# p8x-2016-propplug.net
KiCad netlist of a schematic drawn in EAGLE
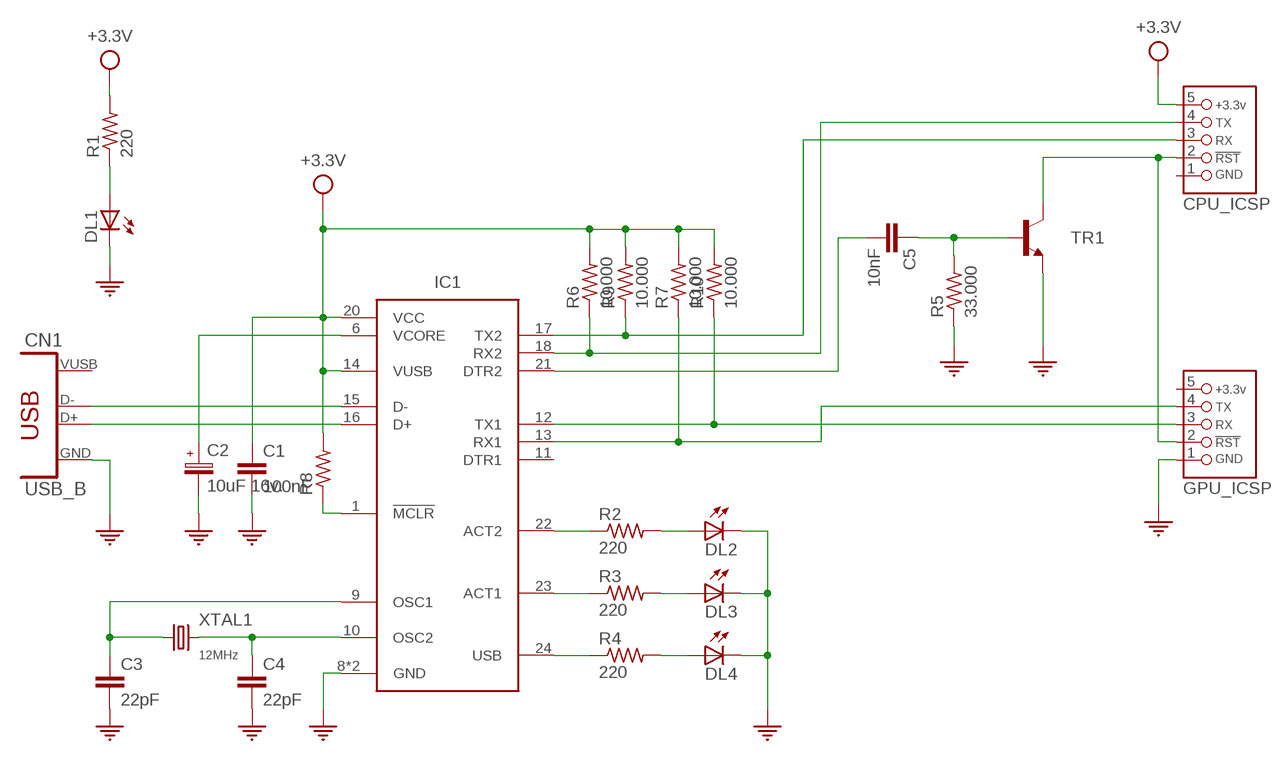
[diagram p0: schematic, sheet 1]

(export (version "E")
  (design (tool "Eeschema 10.0.6"))
  (components
    (comp (ref "C1")
      (value "100nF")
      (footprint "eagle-import:C050-025X075")
      (libsource (lib "eagle-import") (part "C"))
    )
    (comp (ref "C2")
      (value "10uF 16v.")
      (footprint "eagle-import:E2,5-6")
      (libsource (lib "eagle-import") (part "CP-2.5-6"))
    )
    (comp (ref "C3")
      (value "22pF")
      (footprint "eagle-import:C050-025X075D")
      (libsource (lib "eagle-import") (part "C-DISC"))
    )
    (comp (ref "C4")
      (value "22pF")
      (footprint "eagle-import:C050-025X075D")
      (libsource (lib "eagle-import") (part "C-DISC"))
    )
    (comp (ref "C5")
      (value "10nF")
      (footprint "eagle-import:C050-025X075")
      (libsource (lib "eagle-import") (part "C"))
    )
    (comp (ref "CN1")
      (value "USB_B")
      (footprint "eagle-import:USB-B")
      (libsource (lib "eagle-import") (part "USB_B"))
    )
    (comp (ref "CPU_ICSP")
      (value "PROPELLER_ICSP_HEADER")
      (footprint "eagle-import:HEADER_PRG_1X05")
      (libsource (lib "eagle-import") (part "PROPELLER_ICSP_HEADER"))
    )
    (comp (ref "DL1")
      (value "LED-3MM")
      (footprint "eagle-import:LED3MM")
      (libsource (lib "eagle-import") (part "LED-3MM"))
    )
    (comp (ref "DL2")
      (value "LED-3MM")
      (footprint "eagle-import:LED3MM")
      (libsource (lib "eagle-import") (part "LED-3MM"))
    )
    (comp (ref "DL3")
      (value "LED-3MM")
      (footprint "eagle-import:LED3MM")
      (libsource (lib "eagle-import") (part "LED-3MM"))
    )
    (comp (ref "DL4")
      (value "LED-3MM")
      (footprint "eagle-import:LED3MM")
      (libsource (lib "eagle-import") (part "LED-3MM"))
    )
    (comp (ref "GPU_ICSP")
      (value "PROPELLER_ICSP_HEADER")
      (footprint "eagle-import:HEADER_PRG_1X05")
      (libsource (lib "eagle-import") (part "PROPELLER_ICSP_HEADER"))
    )
    (comp (ref "IC1")
      (value "PIC18F24J50-I/P")
      (footprint "eagle-import:DIL28")
      (libsource (lib "eagle-import") (part "PIC18F24J50-I/P"))
    )
    (comp (ref "R1")
      (value "220")
      (footprint "eagle-import:0207_10")
      (libsource (lib "eagle-import") (part "R-1/4W"))
    )
    (comp (ref "R2")
      (value "220")
      (footprint "eagle-import:0207_10")
      (libsource (lib "eagle-import") (part "R-1/4W"))
    )
    (comp (ref "R3")
      (value "220")
      (footprint "eagle-import:0207_10")
      (libsource (lib "eagle-import") (part "R-1/4W"))
    )
    (comp (ref "R4")
      (value "220")
      (footprint "eagle-import:0207_10")
      (libsource (lib "eagle-import") (part "R-1/4W"))
    )
    (comp (ref "R5")
      (value "33.000")
      (footprint "eagle-import:0207_10")
      (libsource (lib "eagle-import") (part "R-1/4W"))
    )
    (comp (ref "R6")
      (value "10.000")
      (footprint "eagle-import:0207_10")
      (libsource (lib "eagle-import") (part "R-1/4W"))
    )
    (comp (ref "R7")
      (value "10.000")
      (footprint "eagle-import:0207_10")
      (libsource (lib "eagle-import") (part "R-1/4W"))
    )
    (comp (ref "R8")
      (value "R-1/4W")
      (footprint "eagle-import:0207_10")
      (libsource (lib "eagle-import") (part "R-1/4W"))
    )
    (comp (ref "R9")
      (value "10.000")
      (footprint "eagle-import:0207_10")
      (libsource (lib "eagle-import") (part "R-1/4W"))
    )
    (comp (ref "R10")
      (value "10.000")
      (footprint "eagle-import:0207_10")
      (libsource (lib "eagle-import") (part "R-1/4W"))
    )
    (comp (ref "TR1")
      (value "BC547")
      (footprint "eagle-import:TO92")
      (libsource (lib "eagle-import") (part "BC547"))
    )
    (comp (ref "XTAL1")
      (value "12MHz")
      (footprint "eagle-import:HC49_S")
      (libsource (lib "eagle-import") (part "CRYSTAL-HC49/S"))
    )
  )
  (nets
    (net (code "1") (name "+3.3V") (class "Default")
      (node (ref "C1") (pin "1") (pinfunction "1_1") (pintype "passive"))
      (node (ref "CPU_ICSP") (pin "5") (pinfunction "5_5") (pintype "power_in"))
      (node (ref "IC1") (pin "14") (pinfunction "VUSB_14") (pintype "bidirectional"))
      (node (ref "IC1") (pin "20") (pinfunction "VCC_20") (pintype "power_in"))
      (node (ref "R1") (pin "2") (pinfunction "2_2") (pintype "passive"))
      (node (ref "R10") (pin "2") (pinfunction "2_2") (pintype "passive"))
      (node (ref "R6") (pin "2") (pinfunction "2_2") (pintype "passive"))
      (node (ref "R7") (pin "2") (pinfunction "2_2") (pintype "passive"))
      (node (ref "R8") (pin "2") (pinfunction "2_2") (pintype "passive"))
      (node (ref "R9") (pin "2") (pinfunction "2_2") (pintype "passive"))
    )
    (net (code "2") (name "/1") (class "Default")
      (node (ref "CPU_ICSP") (pin "1") (pinfunction "1_1") (pintype "power_in"))
    )
    (net (code "3") (name "/5") (class "Default")
      (node (ref "GPU_ICSP") (pin "5") (pinfunction "5_5") (pintype "power_in"))
    )
    (net (code "4") (name "/VUSB") (class "Default")
      (node (ref "CN1") (pin "1") (pinfunction "VUSB_1") (pintype "power_in"))
    )
    (net (code "5") (name "GND") (class "Default")
      (node (ref "C1") (pin "2") (pinfunction "2_2") (pintype "passive"))
      (node (ref "C2") (pin "-") (pinfunction "-_-") (pintype "passive"))
      (node (ref "C3") (pin "2") (pinfunction "2_2") (pintype "passive"))
      (node (ref "C4") (pin "2") (pinfunction "2_2") (pintype "passive"))
      (node (ref "CN1") (pin "4") (pinfunction "GND_4") (pintype "power_in"))
      (node (ref "DL1") (pin "K") (pinfunction "C_K") (pintype "passive"))
      (node (ref "DL2") (pin "K") (pinfunction "C_K") (pintype "passive"))
      (node (ref "DL3") (pin "K") (pinfunction "C_K") (pintype "passive"))
      (node (ref "DL4") (pin "K") (pinfunction "C_K") (pintype "passive"))
      (node (ref "GPU_ICSP") (pin "1") (pinfunction "1_1") (pintype "power_in"))
      (node (ref "IC1") (pin "19") (pinfunction "GND_19") (pintype "power_in"))
      (node (ref "IC1") (pin "8") (pinfunction "GND_8") (pintype "power_in"))
      (node (ref "R5") (pin "1") (pinfunction "1_1") (pintype "passive"))
      (node (ref "TR1") (pin "1") (pinfunction "E_1") (pintype "passive"))
    )
    (net (code "6") (name "Net-(CN1-D+)") (class "Default")
      (node (ref "CN1") (pin "3") (pinfunction "D+_3") (pintype "bidirectional"))
      (node (ref "IC1") (pin "16") (pinfunction "D+_16") (pintype "bidirectional"))
    )
    (net (code "7") (name "Net-(CN1-D-)") (class "Default")
      (node (ref "CN1") (pin "2") (pinfunction "D-_2") (pintype "bidirectional"))
      (node (ref "IC1") (pin "15") (pinfunction "D-_15") (pintype "bidirectional"))
    )
    (net (code "8") (name "Net-(DL1-PadA)") (class "Default")
      (node (ref "DL1") (pin "A") (pinfunction "A_A") (pintype "passive"))
      (node (ref "R1") (pin "1") (pinfunction "1_1") (pintype "passive"))
    )
    (net (code "9") (name "Net-(DL2-PadA)") (class "Default")
      (node (ref "DL2") (pin "A") (pinfunction "A_A") (pintype "passive"))
      (node (ref "R2") (pin "2") (pinfunction "2_2") (pintype "passive"))
    )
    (net (code "10") (name "Net-(DL3-PadA)") (class "Default")
      (node (ref "DL3") (pin "A") (pinfunction "A_A") (pintype "passive"))
      (node (ref "R3") (pin "2") (pinfunction "2_2") (pintype "passive"))
    )
    (net (code "11") (name "Net-(DL4-PadA)") (class "Default")
      (node (ref "DL4") (pin "A") (pinfunction "A_A") (pintype "passive"))
      (node (ref "R4") (pin "2") (pinfunction "2_2") (pintype "passive"))
    )
    (net (code "12") (name "Net-(IC1-ACT1)") (class "Default")
      (node (ref "IC1") (pin "23") (pinfunction "ACT1_23") (pintype "bidirectional"))
      (node (ref "R3") (pin "1") (pinfunction "1_1") (pintype "passive"))
    )
    (net (code "13") (name "Net-(IC1-ACT2)") (class "Default")
      (node (ref "IC1") (pin "22") (pinfunction "ACT2_22") (pintype "bidirectional"))
      (node (ref "R2") (pin "1") (pinfunction "1_1") (pintype "passive"))
    )
    (net (code "14") (name "Net-(IC1-DTR2)") (class "Default")
      (node (ref "C5") (pin "2") (pinfunction "2_2") (pintype "passive"))
      (node (ref "IC1") (pin "21") (pinfunction "DTR2_21") (pintype "bidirectional"))
    )
    (net (code "15") (name "Net-(IC1-OSC1)") (class "Default")
      (node (ref "C3") (pin "1") (pinfunction "1_1") (pintype "passive"))
      (node (ref "IC1") (pin "9") (pinfunction "OSC1_9") (pintype "bidirectional"))
      (node (ref "XTAL1") (pin "1") (pinfunction "1_1") (pintype "passive"))
    )
    (net (code "16") (name "Net-(IC1-OSC2)") (class "Default")
      (node (ref "C4") (pin "1") (pinfunction "1_1") (pintype "passive"))
      (node (ref "IC1") (pin "10") (pinfunction "OSC2_10") (pintype "bidirectional"))
      (node (ref "XTAL1") (pin "2") (pinfunction "2_2") (pintype "passive"))
    )
    (net (code "17") (name "Net-(IC1-RX1)") (class "Default")
      (node (ref "GPU_ICSP") (pin "4") (pinfunction "4_4") (pintype "output"))
      (node (ref "IC1") (pin "13") (pinfunction "RX1_13") (pintype "bidirectional"))
      (node (ref "R7") (pin "1") (pinfunction "1_1") (pintype "passive"))
    )
    (net (code "18") (name "Net-(IC1-RX2)") (class "Default")
      (node (ref "CPU_ICSP") (pin "4") (pinfunction "4_4") (pintype "output"))
      (node (ref "IC1") (pin "18") (pinfunction "RX2_18") (pintype "bidirectional"))
      (node (ref "R6") (pin "1") (pinfunction "1_1") (pintype "passive"))
    )
    (net (code "19") (name "Net-(IC1-TX1)") (class "Default")
      (node (ref "GPU_ICSP") (pin "3") (pinfunction "3_3") (pintype "input"))
      (node (ref "IC1") (pin "12") (pinfunction "TX1_12") (pintype "bidirectional"))
      (node (ref "R10") (pin "1") (pinfunction "1_1") (pintype "passive"))
    )
    (net (code "20") (name "Net-(IC1-TX2)") (class "Default")
      (node (ref "CPU_ICSP") (pin "3") (pinfunction "3_3") (pintype "input"))
      (node (ref "IC1") (pin "17") (pinfunction "TX2_17") (pintype "bidirectional"))
      (node (ref "R9") (pin "1") (pinfunction "1_1") (pintype "passive"))
    )
    (net (code "21") (name "Net-(IC1-USB)") (class "Default")
      (node (ref "IC1") (pin "24") (pinfunction "USB_24") (pintype "bidirectional"))
      (node (ref "R4") (pin "1") (pinfunction "1_1") (pintype "passive"))
    )
    (net (code "22") (name "Net-(IC1-VCORE)") (class "Default")
      (node (ref "C2") (pin "+") (pinfunction "+_+") (pintype "passive"))
      (node (ref "IC1") (pin "6") (pinfunction "VCORE_6") (pintype "power_in"))
    )
    (net (code "23") (name "Net-(IC1-~{MCLR})") (class "Default")
      (node (ref "IC1") (pin "1") (pinfunction "~{MCLR}_1") (pintype "bidirectional"))
      (node (ref "R8") (pin "1") (pinfunction "1_1") (pintype "passive"))
    )
    (net (code "24") (name "Net-(TR1-B)") (class "Default")
      (node (ref "C5") (pin "1") (pinfunction "1_1") (pintype "passive"))
      (node (ref "R5") (pin "2") (pinfunction "2_2") (pintype "passive"))
      (node (ref "TR1") (pin "2") (pinfunction "B_2") (pintype "passive"))
    )
    (net (code "25") (name "Net-(TR1-C)") (class "Default")
      (node (ref "CPU_ICSP") (pin "2") (pinfunction "2_2") (pintype "input"))
      (node (ref "GPU_ICSP") (pin "2") (pinfunction "2_2") (pintype "input"))
      (node (ref "TR1") (pin "3") (pinfunction "C_3") (pintype "passive"))
    )
    (net (code "26") (name "unconnected-(IC1-DTR1-Pad11)") (class "Default")
      (node (ref "IC1") (pin "11") (pinfunction "DTR1_11") (pintype "bidirectional"))
    )
  )
)
